# sdcard.net
KiCad netlist of a schematic drawn in EAGLE
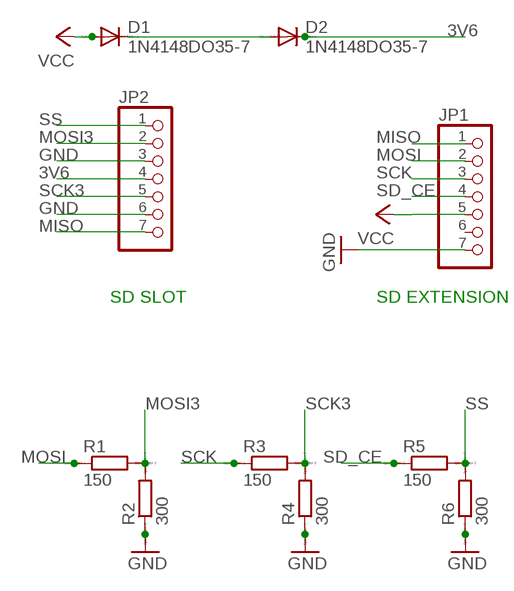
[diagram p0: schematic, sheet 1]

(export (version "E")
  (design (tool "Eeschema 10.0.6"))
  (components
    (comp (ref "D1")
      (value "1N4148DO35-7")
      (footprint "eagle-import:DO35-7")
      (libsource (lib "eagle-import") (part "1N4148DO35-7"))
    )
    (comp (ref "D2")
      (value "1N4148DO35-7")
      (footprint "eagle-import:DO35-7")
      (libsource (lib "eagle-import") (part "1N4148DO35-7"))
    )
    (comp (ref "JP1")
      (value "PINHD-1X7")
      (footprint "eagle-import:1X07")
      (libsource (lib "eagle-import") (part "PINHD-1X7"))
    )
    (comp (ref "JP2")
      (value "PINHD-1X7")
      (footprint "eagle-import:1X07")
      (libsource (lib "eagle-import") (part "PINHD-1X7"))
    )
    (comp (ref "R1")
      (value "150")
      (footprint "eagle-import:R0805")
      (libsource (lib "eagle-import") (part "R-EU_R0805"))
    )
    (comp (ref "R2")
      (value "300")
      (footprint "eagle-import:R0805")
      (libsource (lib "eagle-import") (part "R-EU_R0805"))
    )
    (comp (ref "R3")
      (value "150")
      (footprint "eagle-import:R0805")
      (libsource (lib "eagle-import") (part "R-EU_R0805"))
    )
    (comp (ref "R4")
      (value "300")
      (footprint "eagle-import:R0805")
      (libsource (lib "eagle-import") (part "R-EU_R0805"))
    )
    (comp (ref "R5")
      (value "150")
      (footprint "eagle-import:R0805")
      (libsource (lib "eagle-import") (part "R-EU_R0805"))
    )
    (comp (ref "R6")
      (value "300")
      (footprint "eagle-import:R0805")
      (libsource (lib "eagle-import") (part "R-EU_R0805"))
    )
  )
  (nets
    (net (code "1") (name "/3V6") (class "Default")
      (node (ref "D2") (pin "C") (pinfunction "C_C") (pintype "passive"))
      (node (ref "JP2") (pin "4") (pinfunction "4_4") (pintype "passive"))
    )
    (net (code "2") (name "/MISO") (class "Default")
      (node (ref "JP1") (pin "1") (pinfunction "1_1") (pintype "passive"))
      (node (ref "JP2") (pin "7") (pinfunction "7_7") (pintype "passive"))
    )
    (net (code "3") (name "/MOSI") (class "Default")
      (node (ref "JP1") (pin "2") (pinfunction "2_2") (pintype "passive"))
      (node (ref "R1") (pin "1") (pinfunction "1_1") (pintype "passive"))
    )
    (net (code "4") (name "/MOSI3") (class "Default")
      (node (ref "JP2") (pin "2") (pinfunction "2_2") (pintype "passive"))
      (node (ref "R1") (pin "2") (pinfunction "2_2") (pintype "passive"))
      (node (ref "R2") (pin "2") (pinfunction "2_2") (pintype "passive"))
    )
    (net (code "5") (name "/SCK") (class "Default")
      (node (ref "JP1") (pin "3") (pinfunction "3_3") (pintype "passive"))
      (node (ref "R3") (pin "1") (pinfunction "1_1") (pintype "passive"))
    )
    (net (code "6") (name "/SCK3") (class "Default")
      (node (ref "JP2") (pin "5") (pinfunction "5_5") (pintype "passive"))
      (node (ref "R3") (pin "2") (pinfunction "2_2") (pintype "passive"))
      (node (ref "R4") (pin "2") (pinfunction "2_2") (pintype "passive"))
    )
    (net (code "7") (name "/SD_CE") (class "Default")
      (node (ref "JP1") (pin "4") (pinfunction "4_4") (pintype "passive"))
      (node (ref "R5") (pin "1") (pinfunction "1_1") (pintype "passive"))
    )
    (net (code "8") (name "/SS") (class "Default")
      (node (ref "JP2") (pin "1") (pinfunction "1_1") (pintype "passive"))
      (node (ref "R5") (pin "2") (pinfunction "2_2") (pintype "passive"))
      (node (ref "R6") (pin "2") (pinfunction "2_2") (pintype "passive"))
    )
    (net (code "9") (name "GND") (class "Default")
      (node (ref "JP1") (pin "7") (pinfunction "7_7") (pintype "passive"))
      (node (ref "JP2") (pin "3") (pinfunction "3_3") (pintype "passive"))
      (node (ref "JP2") (pin "6") (pinfunction "6_6") (pintype "passive"))
      (node (ref "R2") (pin "1") (pinfunction "1_1") (pintype "passive"))
      (node (ref "R4") (pin "1") (pinfunction "1_1") (pintype "passive"))
      (node (ref "R6") (pin "1") (pinfunction "1_1") (pintype "passive"))
    )
    (net (code "10") (name "Net-(D1-PadC)") (class "Default")
      (node (ref "D1") (pin "C") (pinfunction "C_C") (pintype "passive"))
      (node (ref "D2") (pin "A") (pinfunction "A_A") (pintype "passive"))
    )
    (net (code "11") (name "VCC") (class "Default")
      (node (ref "D1") (pin "A") (pinfunction "A_A") (pintype "passive"))
      (node (ref "JP1") (pin "5") (pinfunction "5_5") (pintype "passive"))
    )
    (net (code "12") (name "unconnected-(JP1-Pad6)") (class "Default")
      (node (ref "JP1") (pin "6") (pinfunction "6_6") (pintype "passive"))
    )
  )
)
